# PortableWiFiRepeater.net
KiCad netlist of a schematic drawn in EAGLE
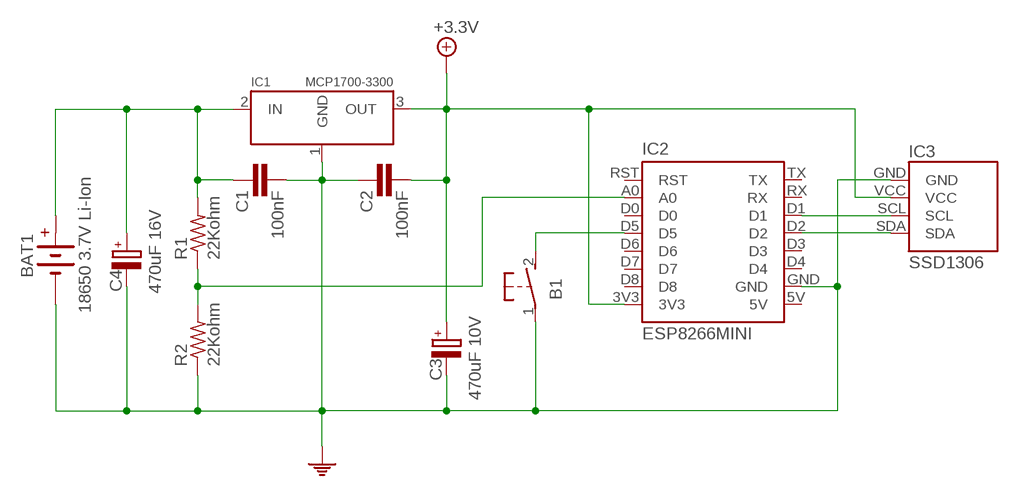
[diagram p0: schematic, sheet 1]

(export (version "E")
  (design (tool "Eeschema 10.0.6"))
  (components
    (comp (ref "B1")
      (value "BUTTONSIL2")
      (footprint "eagle-import:SIL2")
      (libsource (lib "eagle-import") (part "BUTTONSIL2"))
    )
    (comp (ref "BAT1")
      (value "18650 3.7V Li-Ion")
      (footprint "eagle-import:JST2")
      (libsource (lib "eagle-import") (part "BATTERYJST2"))
    )
    (comp (ref "C1")
      (value "100nF")
      (footprint "eagle-import:CAPACITOR-5MM")
      (libsource (lib "eagle-import") (part "CAPACITOR5MM"))
    )
    (comp (ref "C2")
      (value "100nF")
      (footprint "eagle-import:CAPACITOR-5MM")
      (libsource (lib "eagle-import") (part "CAPACITOR5MM"))
    )
    (comp (ref "C3")
      (value "470uF 10V")
      (footprint "eagle-import:CAPACITOR-5MM")
      (libsource (lib "eagle-import") (part "CAPACITOR_EL5MM"))
    )
    (comp (ref "C4")
      (value "470uF 16V")
      (footprint "eagle-import:CAPACITOR-5MM")
      (libsource (lib "eagle-import") (part "CAPACITOR_EL5MM"))
    )
    (comp (ref "IC1")
      (value "MCP1700-3300")
      (footprint "eagle-import:TO92")
      (libsource (lib "eagle-import") (part "MCP1700"))
    )
    (comp (ref "IC2")
      (value "ESP8266MINI")
      (footprint "eagle-import:ESP8266MINI")
      (libsource (lib "eagle-import") (part "ESP8266MINI"))
    )
    (comp (ref "IC3")
      (value "SSD1306")
      (footprint "eagle-import:SSD1306")
      (libsource (lib "eagle-import") (part "SSD1306"))
    )
    (comp (ref "R1")
      (value "22Kohm")
      (footprint "eagle-import:RESISTOR-0.25W")
      (libsource (lib "eagle-import") (part "RESISTOR0.25W"))
    )
    (comp (ref "R2")
      (value "22Kohm")
      (footprint "eagle-import:RESISTOR-0.25W")
      (libsource (lib "eagle-import") (part "RESISTOR0.25W"))
    )
  )
  (nets
    (net (code "1") (name "+3.3V") (class "Default")
      (node (ref "C2") (pin "2") (pinfunction "2_2") (pintype "passive"))
      (node (ref "C3") (pin "1") (pinfunction "1_1") (pintype "passive"))
      (node (ref "IC1") (pin "3") (pinfunction "OUT_3") (pintype "output"))
      (node (ref "IC2") (pin "3V3") (pinfunction "3V3_3V3") (pintype "power_in"))
      (node (ref "IC3") (pin "VCC") (pinfunction "VCC_VCC") (pintype "power_in"))
    )
    (net (code "2") (name "/5V") (class "Default")
      (node (ref "IC2") (pin "5V") (pinfunction "5V_5V") (pintype "power_in"))
    )
    (net (code "3") (name "GND") (class "Default")
      (node (ref "B1") (pin "1") (pinfunction "P_1") (pintype "passive"))
      (node (ref "BAT1") (pin "2") (pinfunction "-_2") (pintype "passive"))
      (node (ref "C1") (pin "2") (pinfunction "2_2") (pintype "passive"))
      (node (ref "C2") (pin "1") (pinfunction "1_1") (pintype "passive"))
      (node (ref "C3") (pin "2") (pinfunction "2_2") (pintype "passive"))
      (node (ref "C4") (pin "2") (pinfunction "2_2") (pintype "passive"))
      (node (ref "IC1") (pin "1") (pinfunction "GND_1") (pintype "power_in"))
      (node (ref "IC2") (pin "GND") (pinfunction "GND_GND") (pintype "power_in"))
      (node (ref "IC3") (pin "GND") (pinfunction "GND_GND") (pintype "power_in"))
      (node (ref "R2") (pin "1") (pinfunction "1_1") (pintype "passive"))
    )
    (net (code "4") (name "Net-(B1-S)") (class "Default")
      (node (ref "B1") (pin "2") (pinfunction "S_2") (pintype "passive"))
      (node (ref "IC2") (pin "D5") (pinfunction "D5_D5") (pintype "bidirectional"))
    )
    (net (code "5") (name "Net-(BAT1-+)") (class "Default")
      (node (ref "BAT1") (pin "1") (pinfunction "+_1") (pintype "passive"))
      (node (ref "C1") (pin "1") (pinfunction "1_1") (pintype "passive"))
      (node (ref "C4") (pin "1") (pinfunction "1_1") (pintype "passive"))
      (node (ref "IC1") (pin "2") (pinfunction "IN_2") (pintype "input"))
      (node (ref "R1") (pin "2") (pinfunction "2_2") (pintype "passive"))
    )
    (net (code "6") (name "Net-(IC2-PadA0)") (class "Default")
      (node (ref "IC2") (pin "A0") (pinfunction "A0_A0") (pintype "bidirectional"))
      (node (ref "R1") (pin "1") (pinfunction "1_1") (pintype "passive"))
      (node (ref "R2") (pin "2") (pinfunction "2_2") (pintype "passive"))
    )
    (net (code "7") (name "Net-(IC2-PadD1)") (class "Default")
      (node (ref "IC2") (pin "D1") (pinfunction "D1_D1") (pintype "bidirectional"))
      (node (ref "IC3") (pin "SCL") (pinfunction "SCL_SCL") (pintype "bidirectional"))
    )
    (net (code "8") (name "Net-(IC2-PadD2)") (class "Default")
      (node (ref "IC2") (pin "D2") (pinfunction "D2_D2") (pintype "bidirectional"))
      (node (ref "IC3") (pin "SDA") (pinfunction "SDA_SDA") (pintype "bidirectional"))
    )
    (net (code "9") (name "unconnected-(IC2-PadD0)") (class "Default")
      (node (ref "IC2") (pin "D0") (pinfunction "D0_D0") (pintype "bidirectional"))
    )
    (net (code "10") (name "unconnected-(IC2-PadD3)") (class "Default")
      (node (ref "IC2") (pin "D3") (pinfunction "D3_D3") (pintype "bidirectional"))
    )
    (net (code "11") (name "unconnected-(IC2-PadD4)") (class "Default")
      (node (ref "IC2") (pin "D4") (pinfunction "D4_D4") (pintype "bidirectional"))
    )
    (net (code "12") (name "unconnected-(IC2-PadD6)") (class "Default")
      (node (ref "IC2") (pin "D6") (pinfunction "D6_D6") (pintype "bidirectional"))
    )
    (net (code "13") (name "unconnected-(IC2-PadD7)") (class "Default")
      (node (ref "IC2") (pin "D7") (pinfunction "D7_D7") (pintype "bidirectional"))
    )
    (net (code "14") (name "unconnected-(IC2-PadD8)") (class "Default")
      (node (ref "IC2") (pin "D8") (pinfunction "D8_D8") (pintype "bidirectional"))
    )
    (net (code "15") (name "unconnected-(IC2-PadRST)") (class "Default")
      (node (ref "IC2") (pin "RST") (pinfunction "RST_RST") (pintype "bidirectional"))
    )
    (net (code "16") (name "unconnected-(IC2-PadRX)") (class "Default")
      (node (ref "IC2") (pin "RX") (pinfunction "RX_RX") (pintype "input"))
    )
    (net (code "17") (name "unconnected-(IC2-PadTX)") (class "Default")
      (node (ref "IC2") (pin "TX") (pinfunction "TX_TX") (pintype "output"))
    )
  )
)
